# datapath.net
KiCad netlist of a schematic drawn in EAGLE
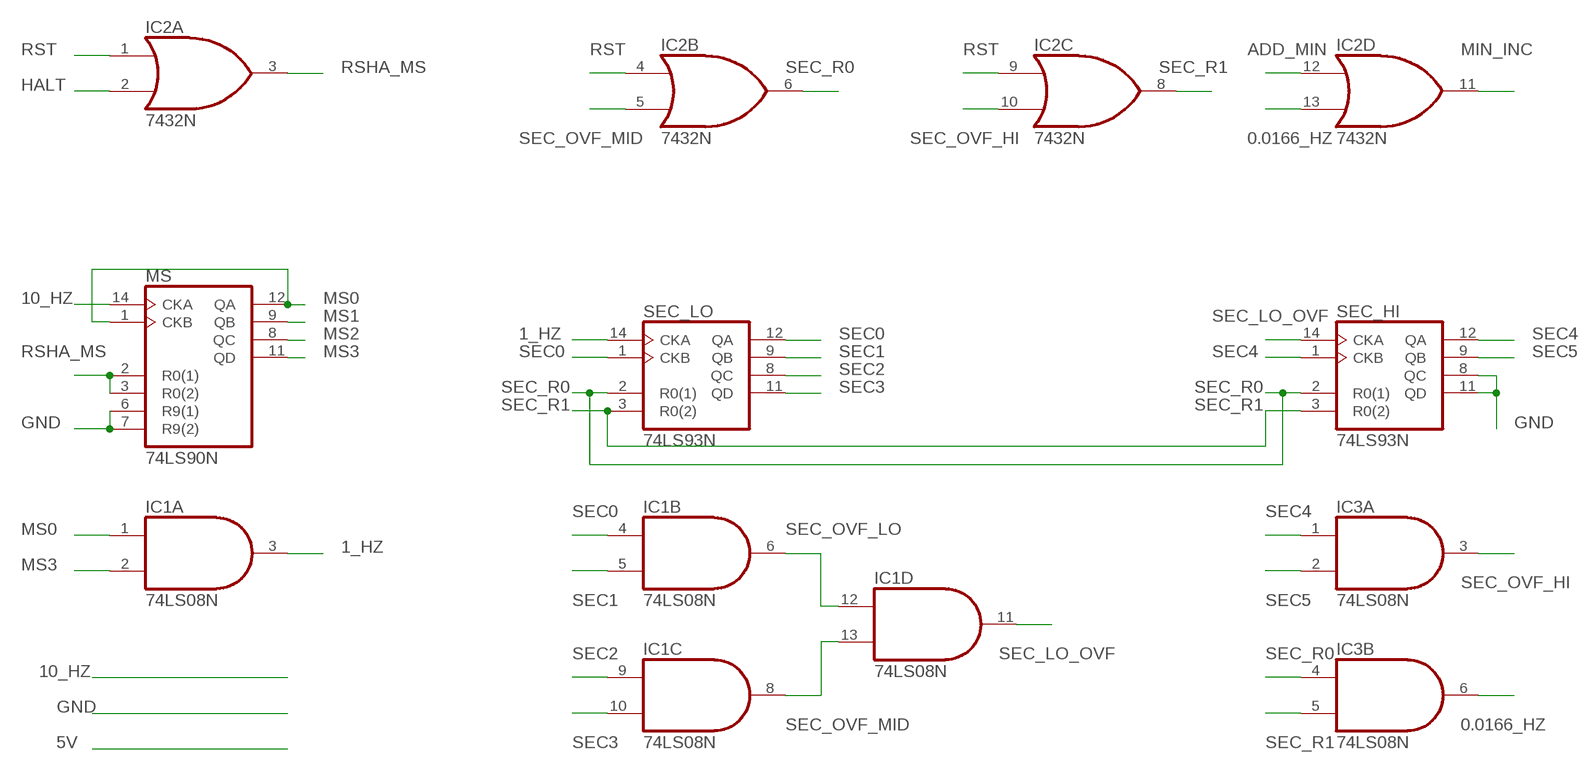
[diagram p0: schematic, sheet 1, part 1 of 2]
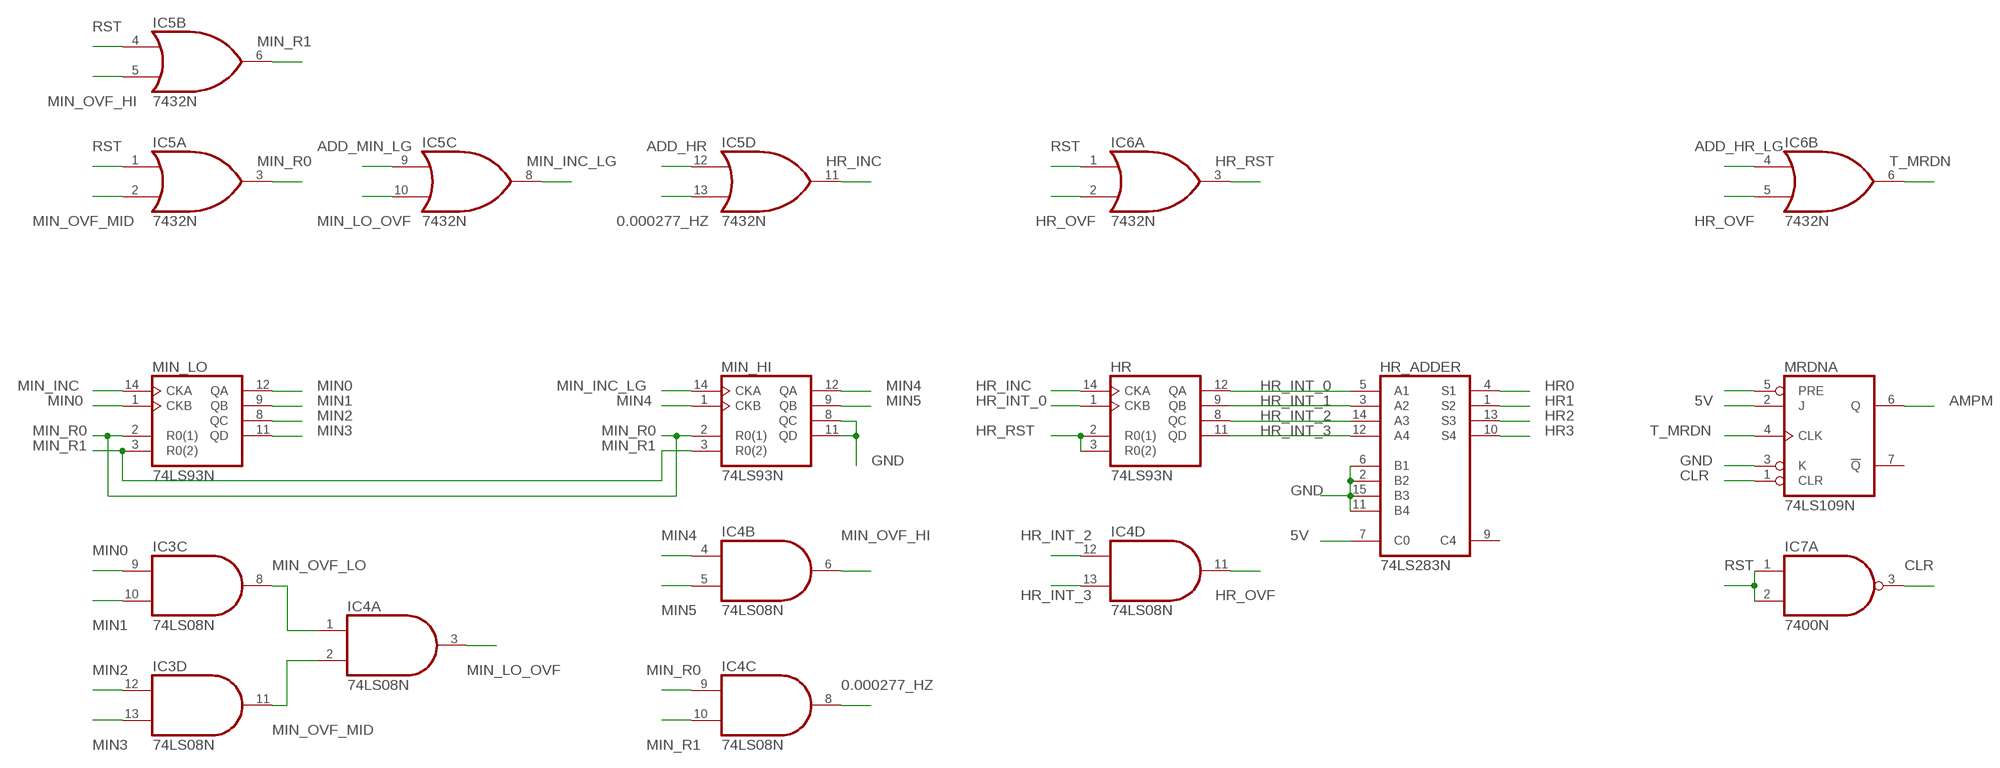
[diagram p1: schematic, sheet 1, part 2 of 2]

(export (version "E")
  (design (tool "Eeschema 10.0.6"))
  (components
    (comp (ref "HR")
      (value "74LS93N")
      (footprint "eagle-import:DIL14")
      (libsource (lib "eagle-import") (part "7493NLS"))
    )
    (comp (ref "HR_ADDER")
      (value "74LS283N")
      (footprint "eagle-import:DIL16")
      (libsource (lib "eagle-import") (part "74283NLS"))
    )
    (comp (ref "IC1")
      (value "74LS08N")
      (footprint "eagle-import:DIL14")
      (libsource (lib "eagle-import") (part "7408NLS"))
    )
    (comp (ref "IC2")
      (value "7432N")
      (footprint "eagle-import:DIL14")
      (libsource (lib "eagle-import") (part "7432N"))
    )
    (comp (ref "IC3")
      (value "74LS08N")
      (footprint "eagle-import:DIL14")
      (libsource (lib "eagle-import") (part "7408NLS"))
    )
    (comp (ref "IC4")
      (value "74LS08N")
      (footprint "eagle-import:DIL14")
      (libsource (lib "eagle-import") (part "7408NLS"))
    )
    (comp (ref "IC5")
      (value "7432N")
      (footprint "eagle-import:DIL14")
      (libsource (lib "eagle-import") (part "7432N"))
    )
    (comp (ref "IC6")
      (value "7432N")
      (footprint "eagle-import:DIL14")
      (libsource (lib "eagle-import") (part "7432N"))
    )
    (comp (ref "IC7")
      (value "7400N")
      (footprint "eagle-import:DIL14")
      (libsource (lib "eagle-import") (part "7400N"))
    )
    (comp (ref "MIN_HI")
      (value "74LS93N")
      (footprint "eagle-import:DIL14")
      (libsource (lib "eagle-import") (part "7493NLS"))
    )
    (comp (ref "MIN_LO")
      (value "74LS93N")
      (footprint "eagle-import:DIL14")
      (libsource (lib "eagle-import") (part "7493NLS"))
    )
    (comp (ref "MRDN")
      (value "74LS109N")
      (footprint "eagle-import:DIL16")
      (libsource (lib "eagle-import") (part "74109NLS"))
    )
    (comp (ref "MS")
      (value "74LS90N")
      (footprint "eagle-import:DIL14")
      (libsource (lib "eagle-import") (part "7490NLS"))
    )
    (comp (ref "SEC_HI")
      (value "74LS93N")
      (footprint "eagle-import:DIL14")
      (libsource (lib "eagle-import") (part "7493NLS"))
    )
    (comp (ref "SEC_LO")
      (value "74LS93N")
      (footprint "eagle-import:DIL14")
      (libsource (lib "eagle-import") (part "7493NLS"))
    )
  )
  (nets
    (net (code "1") (name "/0.0166_HZ") (class "Default")
      (node (ref "IC2") (pin "13") (pinfunction "I1_13") (pintype "input"))
      (node (ref "IC3") (pin "6") (pinfunction "O_6") (pintype "output"))
    )
    (net (code "2") (name "/0.000277_HZ") (class "Default")
      (node (ref "IC4") (pin "8") (pinfunction "O_8") (pintype "output"))
      (node (ref "IC5") (pin "13") (pinfunction "I1_13") (pintype "input"))
    )
    (net (code "3") (name "/1_HZ") (class "Default")
      (node (ref "IC1") (pin "3") (pinfunction "O_3") (pintype "output"))
      (node (ref "SEC_LO") (pin "14") (pinfunction "CKA_14") (pintype "input"))
    )
    (net (code "4") (name "/5V") (class "Default")
      (node (ref "HR_ADDER") (pin "7") (pinfunction "C0_7") (pintype "input"))
      (node (ref "MRDN") (pin "2") (pinfunction "J_2") (pintype "input"))
    )
    (net (code "5") (name "/10_HZ") (class "Default")
      (node (ref "MS") (pin "14") (pinfunction "CKA_14") (pintype "input"))
    )
    (net (code "6") (name "/ADD_HR") (class "Default")
      (node (ref "IC5") (pin "12") (pinfunction "I0_12") (pintype "input"))
    )
    (net (code "7") (name "/ADD_HR_LG") (class "Default")
      (node (ref "IC6") (pin "4") (pinfunction "I0_4") (pintype "input"))
    )
    (net (code "8") (name "/ADD_MIN") (class "Default")
      (node (ref "IC2") (pin "12") (pinfunction "I0_12") (pintype "input"))
    )
    (net (code "9") (name "/ADD_MIN_LG") (class "Default")
      (node (ref "IC5") (pin "9") (pinfunction "I0_9") (pintype "input"))
    )
    (net (code "10") (name "/AMPM") (class "Default")
      (node (ref "MRDN") (pin "6") (pinfunction "Q_6") (pintype "output"))
    )
    (net (code "11") (name "/CLR") (class "Default")
      (node (ref "IC7") (pin "3") (pinfunction "O_3") (pintype "output"))
      (node (ref "MRDN") (pin "1") (pinfunction "CLR_1") (pintype "input"))
    )
    (net (code "12") (name "/GND") (class "Default")
      (node (ref "HR_ADDER") (pin "11") (pinfunction "B4_11") (pintype "input"))
      (node (ref "HR_ADDER") (pin "15") (pinfunction "B3_15") (pintype "input"))
      (node (ref "HR_ADDER") (pin "2") (pinfunction "B2_2") (pintype "input"))
      (node (ref "HR_ADDER") (pin "6") (pinfunction "B1_6") (pintype "input"))
      (node (ref "MIN_HI") (pin "11") (pinfunction "QD_11") (pintype "output"))
      (node (ref "MIN_HI") (pin "8") (pinfunction "QC_8") (pintype "output"))
      (node (ref "MRDN") (pin "3") (pinfunction "K_3") (pintype "input"))
      (node (ref "MS") (pin "6") (pinfunction "R9(1)_6") (pintype "input"))
      (node (ref "MS") (pin "7") (pinfunction "R9(2)_7") (pintype "input"))
      (node (ref "SEC_HI") (pin "11") (pinfunction "QD_11") (pintype "output"))
      (node (ref "SEC_HI") (pin "8") (pinfunction "QC_8") (pintype "output"))
    )
    (net (code "13") (name "/HALT") (class "Default")
      (node (ref "IC2") (pin "2") (pinfunction "I1_2") (pintype "input"))
    )
    (net (code "14") (name "/HR0") (class "Default")
      (node (ref "HR_ADDER") (pin "4") (pinfunction "S1_4") (pintype "output"))
    )
    (net (code "15") (name "/HR1") (class "Default")
      (node (ref "HR_ADDER") (pin "1") (pinfunction "S2_1") (pintype "output"))
    )
    (net (code "16") (name "/HR2") (class "Default")
      (node (ref "HR_ADDER") (pin "13") (pinfunction "S3_13") (pintype "output"))
    )
    (net (code "17") (name "/HR3") (class "Default")
      (node (ref "HR_ADDER") (pin "10") (pinfunction "S4_10") (pintype "output"))
    )
    (net (code "18") (name "/HR_INC") (class "Default")
      (node (ref "HR") (pin "14") (pinfunction "CKA_14") (pintype "input"))
      (node (ref "IC5") (pin "11") (pinfunction "O_11") (pintype "output"))
    )
    (net (code "19") (name "/HR_INT_0") (class "Default")
      (node (ref "HR") (pin "1") (pinfunction "CKB_1") (pintype "input"))
      (node (ref "HR") (pin "12") (pinfunction "QA_12") (pintype "output"))
      (node (ref "HR_ADDER") (pin "5") (pinfunction "A1_5") (pintype "input"))
    )
    (net (code "20") (name "/HR_INT_1") (class "Default")
      (node (ref "HR") (pin "9") (pinfunction "QB_9") (pintype "output"))
      (node (ref "HR_ADDER") (pin "3") (pinfunction "A2_3") (pintype "input"))
    )
    (net (code "21") (name "/HR_INT_2") (class "Default")
      (node (ref "HR") (pin "8") (pinfunction "QC_8") (pintype "output"))
      (node (ref "HR_ADDER") (pin "14") (pinfunction "A3_14") (pintype "input"))
      (node (ref "IC4") (pin "12") (pinfunction "I0_12") (pintype "input"))
    )
    (net (code "22") (name "/HR_INT_3") (class "Default")
      (node (ref "HR") (pin "11") (pinfunction "QD_11") (pintype "output"))
      (node (ref "HR_ADDER") (pin "12") (pinfunction "A4_12") (pintype "input"))
      (node (ref "IC4") (pin "13") (pinfunction "I1_13") (pintype "input"))
    )
    (net (code "23") (name "/HR_OVF") (class "Default")
      (node (ref "IC4") (pin "11") (pinfunction "O_11") (pintype "output"))
      (node (ref "IC6") (pin "2") (pinfunction "I1_2") (pintype "input"))
      (node (ref "IC6") (pin "5") (pinfunction "I1_5") (pintype "input"))
    )
    (net (code "24") (name "/HR_RST") (class "Default")
      (node (ref "HR") (pin "2") (pinfunction "R0(1)_2") (pintype "input"))
      (node (ref "HR") (pin "3") (pinfunction "R0(2)_3") (pintype "input"))
      (node (ref "IC6") (pin "3") (pinfunction "O_3") (pintype "output"))
    )
    (net (code "25") (name "/MIN0") (class "Default")
      (node (ref "IC3") (pin "9") (pinfunction "I0_9") (pintype "input"))
      (node (ref "MIN_LO") (pin "1") (pinfunction "CKB_1") (pintype "input"))
      (node (ref "MIN_LO") (pin "12") (pinfunction "QA_12") (pintype "output"))
    )
    (net (code "26") (name "/MIN1") (class "Default")
      (node (ref "IC3") (pin "10") (pinfunction "I1_10") (pintype "input"))
      (node (ref "MIN_LO") (pin "9") (pinfunction "QB_9") (pintype "output"))
    )
    (net (code "27") (name "/MIN2") (class "Default")
      (node (ref "IC3") (pin "12") (pinfunction "I0_12") (pintype "input"))
      (node (ref "MIN_LO") (pin "8") (pinfunction "QC_8") (pintype "output"))
    )
    (net (code "28") (name "/MIN3") (class "Default")
      (node (ref "IC3") (pin "13") (pinfunction "I1_13") (pintype "input"))
      (node (ref "MIN_LO") (pin "11") (pinfunction "QD_11") (pintype "output"))
    )
    (net (code "29") (name "/MIN4") (class "Default")
      (node (ref "IC4") (pin "4") (pinfunction "I0_4") (pintype "input"))
      (node (ref "MIN_HI") (pin "1") (pinfunction "CKB_1") (pintype "input"))
      (node (ref "MIN_HI") (pin "12") (pinfunction "QA_12") (pintype "output"))
    )
    (net (code "30") (name "/MIN5") (class "Default")
      (node (ref "IC4") (pin "5") (pinfunction "I1_5") (pintype "input"))
      (node (ref "MIN_HI") (pin "9") (pinfunction "QB_9") (pintype "output"))
    )
    (net (code "31") (name "/MIN_INC") (class "Default")
      (node (ref "IC2") (pin "11") (pinfunction "O_11") (pintype "output"))
      (node (ref "MIN_LO") (pin "14") (pinfunction "CKA_14") (pintype "input"))
    )
    (net (code "32") (name "/MIN_INC_LG") (class "Default")
      (node (ref "IC5") (pin "8") (pinfunction "O_8") (pintype "output"))
      (node (ref "MIN_HI") (pin "14") (pinfunction "CKA_14") (pintype "input"))
    )
    (net (code "33") (name "/MIN_LO_OVF") (class "Default")
      (node (ref "IC4") (pin "3") (pinfunction "O_3") (pintype "output"))
      (node (ref "IC5") (pin "10") (pinfunction "I1_10") (pintype "input"))
    )
    (net (code "34") (name "/MIN_OVF_HI") (class "Default")
      (node (ref "IC4") (pin "6") (pinfunction "O_6") (pintype "output"))
      (node (ref "IC5") (pin "5") (pinfunction "I1_5") (pintype "input"))
    )
    (net (code "35") (name "/MIN_OVF_LO") (class "Default")
      (node (ref "IC3") (pin "8") (pinfunction "O_8") (pintype "output"))
      (node (ref "IC4") (pin "1") (pinfunction "I0_1") (pintype "input"))
    )
    (net (code "36") (name "/MIN_OVF_MID") (class "Default")
      (node (ref "IC3") (pin "11") (pinfunction "O_11") (pintype "output"))
      (node (ref "IC4") (pin "2") (pinfunction "I1_2") (pintype "input"))
      (node (ref "IC5") (pin "2") (pinfunction "I1_2") (pintype "input"))
    )
    (net (code "37") (name "/MIN_R0") (class "Default")
      (node (ref "IC4") (pin "9") (pinfunction "I0_9") (pintype "input"))
      (node (ref "IC5") (pin "3") (pinfunction "O_3") (pintype "output"))
      (node (ref "MIN_HI") (pin "2") (pinfunction "R0(1)_2") (pintype "input"))
      (node (ref "MIN_LO") (pin "2") (pinfunction "R0(1)_2") (pintype "input"))
    )
    (net (code "38") (name "/MIN_R1") (class "Default")
      (node (ref "IC4") (pin "10") (pinfunction "I1_10") (pintype "input"))
      (node (ref "IC5") (pin "6") (pinfunction "O_6") (pintype "output"))
      (node (ref "MIN_HI") (pin "3") (pinfunction "R0(2)_3") (pintype "input"))
      (node (ref "MIN_LO") (pin "3") (pinfunction "R0(2)_3") (pintype "input"))
    )
    (net (code "39") (name "/MS0") (class "Default")
      (node (ref "IC1") (pin "1") (pinfunction "I0_1") (pintype "input"))
      (node (ref "MS") (pin "1") (pinfunction "CKB_1") (pintype "input"))
      (node (ref "MS") (pin "12") (pinfunction "QA_12") (pintype "output"))
    )
    (net (code "40") (name "/MS1") (class "Default")
      (node (ref "MS") (pin "9") (pinfunction "QB_9") (pintype "output"))
    )
    (net (code "41") (name "/MS2") (class "Default")
      (node (ref "MS") (pin "8") (pinfunction "QC_8") (pintype "output"))
    )
    (net (code "42") (name "/MS3") (class "Default")
      (node (ref "IC1") (pin "2") (pinfunction "I1_2") (pintype "input"))
      (node (ref "MS") (pin "11") (pinfunction "QD_11") (pintype "output"))
    )
    (net (code "43") (name "/RSHA_MS") (class "Default")
      (node (ref "IC2") (pin "3") (pinfunction "O_3") (pintype "output"))
      (node (ref "MS") (pin "2") (pinfunction "R0(1)_2") (pintype "input"))
      (node (ref "MS") (pin "3") (pinfunction "R0(2)_3") (pintype "input"))
    )
    (net (code "44") (name "/RST") (class "Default")
      (node (ref "IC2") (pin "1") (pinfunction "I0_1") (pintype "input"))
      (node (ref "IC2") (pin "4") (pinfunction "I0_4") (pintype "input"))
      (node (ref "IC2") (pin "9") (pinfunction "I0_9") (pintype "input"))
      (node (ref "IC5") (pin "1") (pinfunction "I0_1") (pintype "input"))
      (node (ref "IC5") (pin "4") (pinfunction "I0_4") (pintype "input"))
      (node (ref "IC6") (pin "1") (pinfunction "I0_1") (pintype "input"))
      (node (ref "IC7") (pin "1") (pinfunction "I0_1") (pintype "input"))
      (node (ref "IC7") (pin "2") (pinfunction "I1_2") (pintype "input"))
    )
    (net (code "45") (name "/SEC0") (class "Default")
      (node (ref "IC1") (pin "4") (pinfunction "I0_4") (pintype "input"))
      (node (ref "SEC_LO") (pin "1") (pinfunction "CKB_1") (pintype "input"))
      (node (ref "SEC_LO") (pin "12") (pinfunction "QA_12") (pintype "output"))
    )
    (net (code "46") (name "/SEC1") (class "Default")
      (node (ref "IC1") (pin "5") (pinfunction "I1_5") (pintype "input"))
      (node (ref "SEC_LO") (pin "9") (pinfunction "QB_9") (pintype "output"))
    )
    (net (code "47") (name "/SEC2") (class "Default")
      (node (ref "IC1") (pin "9") (pinfunction "I0_9") (pintype "input"))
      (node (ref "SEC_LO") (pin "8") (pinfunction "QC_8") (pintype "output"))
    )
    (net (code "48") (name "/SEC3") (class "Default")
      (node (ref "IC1") (pin "10") (pinfunction "I1_10") (pintype "input"))
      (node (ref "SEC_LO") (pin "11") (pinfunction "QD_11") (pintype "output"))
    )
    (net (code "49") (name "/SEC4") (class "Default")
      (node (ref "IC3") (pin "1") (pinfunction "I0_1") (pintype "input"))
      (node (ref "SEC_HI") (pin "1") (pinfunction "CKB_1") (pintype "input"))
      (node (ref "SEC_HI") (pin "12") (pinfunction "QA_12") (pintype "output"))
    )
    (net (code "50") (name "/SEC5") (class "Default")
      (node (ref "IC3") (pin "2") (pinfunction "I1_2") (pintype "input"))
      (node (ref "SEC_HI") (pin "9") (pinfunction "QB_9") (pintype "output"))
    )
    (net (code "51") (name "/SEC_LO_OVF") (class "Default")
      (node (ref "IC1") (pin "11") (pinfunction "O_11") (pintype "output"))
      (node (ref "SEC_HI") (pin "14") (pinfunction "CKA_14") (pintype "input"))
    )
    (net (code "52") (name "/SEC_OVF_HI") (class "Default")
      (node (ref "IC2") (pin "10") (pinfunction "I1_10") (pintype "input"))
      (node (ref "IC3") (pin "3") (pinfunction "O_3") (pintype "output"))
    )
    (net (code "53") (name "/SEC_OVF_LO") (class "Default")
      (node (ref "IC1") (pin "12") (pinfunction "I0_12") (pintype "input"))
      (node (ref "IC1") (pin "6") (pinfunction "O_6") (pintype "output"))
    )
    (net (code "54") (name "/SEC_OVF_MID") (class "Default")
      (node (ref "IC1") (pin "13") (pinfunction "I1_13") (pintype "input"))
      (node (ref "IC1") (pin "8") (pinfunction "O_8") (pintype "output"))
      (node (ref "IC2") (pin "5") (pinfunction "I1_5") (pintype "input"))
    )
    (net (code "55") (name "/SEC_R0") (class "Default")
      (node (ref "IC2") (pin "6") (pinfunction "O_6") (pintype "output"))
      (node (ref "IC3") (pin "4") (pinfunction "I0_4") (pintype "input"))
      (node (ref "SEC_HI") (pin "2") (pinfunction "R0(1)_2") (pintype "input"))
      (node (ref "SEC_LO") (pin "2") (pinfunction "R0(1)_2") (pintype "input"))
    )
    (net (code "56") (name "/SEC_R1") (class "Default")
      (node (ref "IC2") (pin "8") (pinfunction "O_8") (pintype "output"))
      (node (ref "IC3") (pin "5") (pinfunction "I1_5") (pintype "input"))
      (node (ref "SEC_HI") (pin "3") (pinfunction "R0(2)_3") (pintype "input"))
      (node (ref "SEC_LO") (pin "3") (pinfunction "R0(2)_3") (pintype "input"))
    )
    (net (code "57") (name "/T_MRDN") (class "Default")
      (node (ref "IC6") (pin "6") (pinfunction "O_6") (pintype "output"))
      (node (ref "MRDN") (pin "4") (pinfunction "CLK_4") (pintype "input"))
    )
    (net (code "58") (name "unconnected-(HR_ADDERA-C4-Pad9)") (class "Default")
      (node (ref "HR_ADDER") (pin "9") (pinfunction "C4_9") (pintype "output"))
    )
    (net (code "59") (name "unconnected-(MRDNA-PRE-Pad5)") (class "Default")
      (node (ref "MRDN") (pin "5") (pinfunction "PRE_5") (pintype "input"))
    )
    (net (code "60") (name "unconnected-(MRDNA-~{Q}-Pad7)") (class "Default")
      (node (ref "MRDN") (pin "7") (pinfunction "~{Q}_7") (pintype "output"))
    )
  )
)
